# mouse.net
KiCad netlist of a schematic drawn in EasyEDA Pro
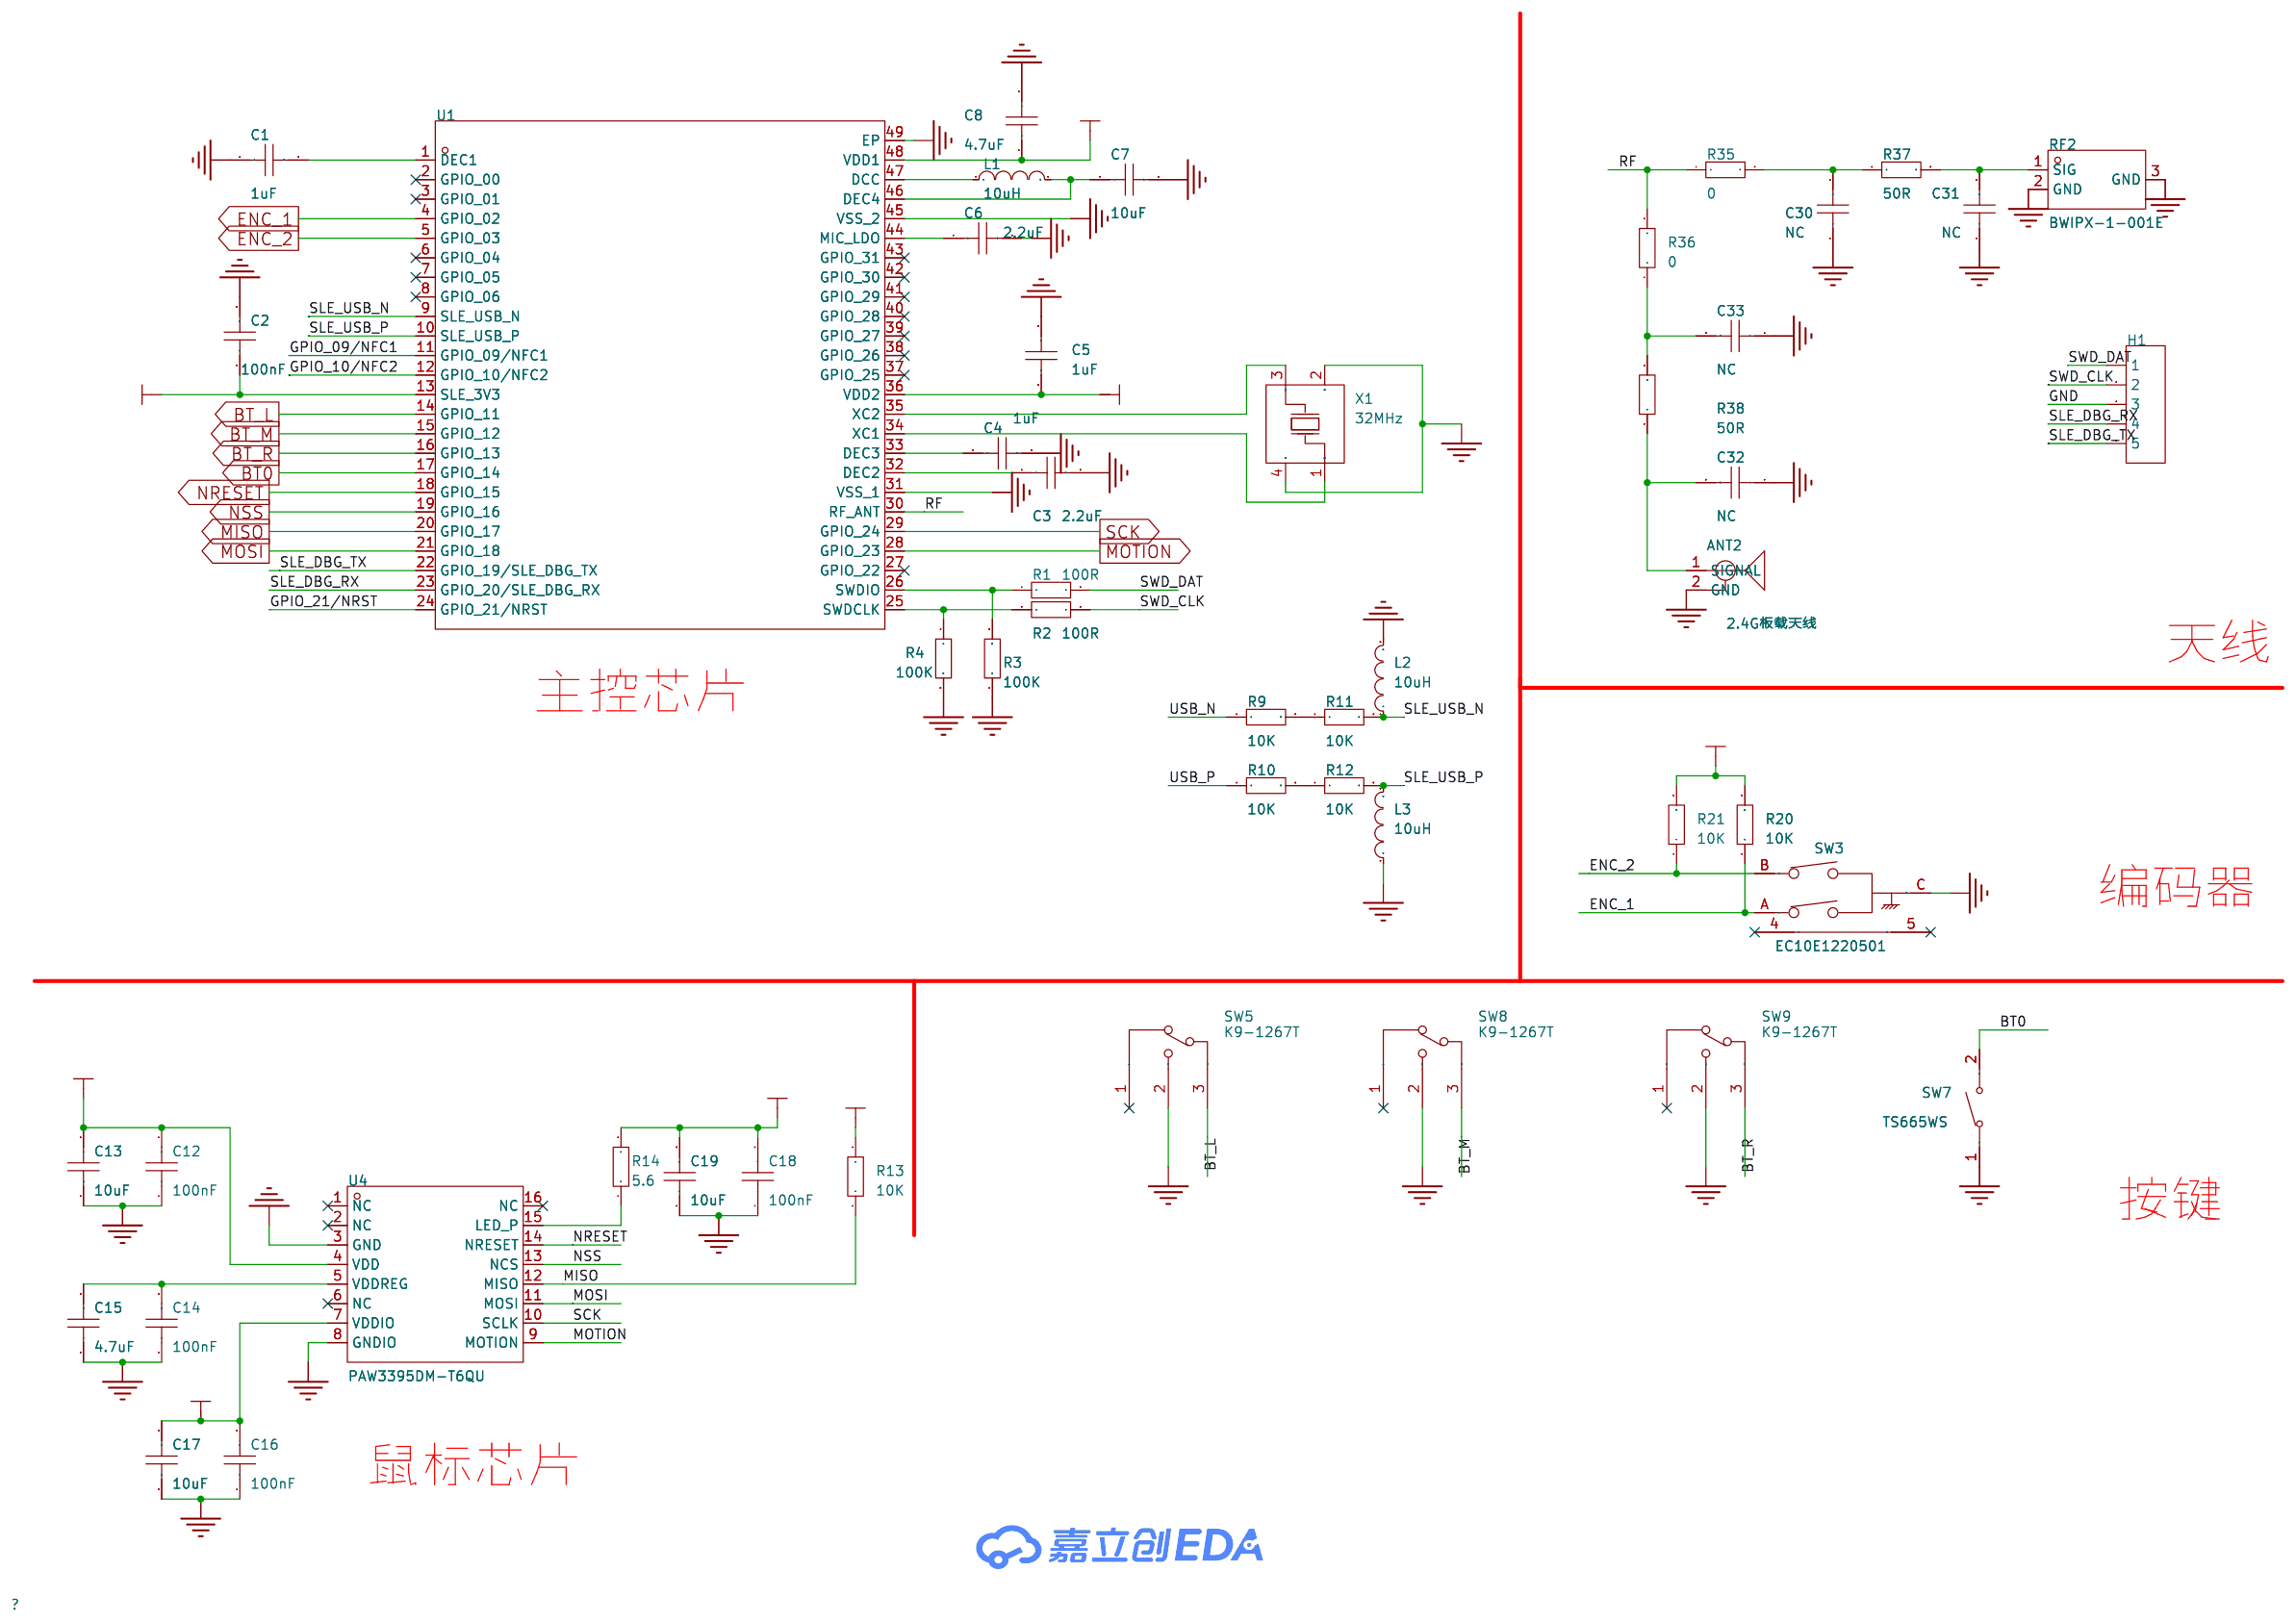
[diagram p0: P1]
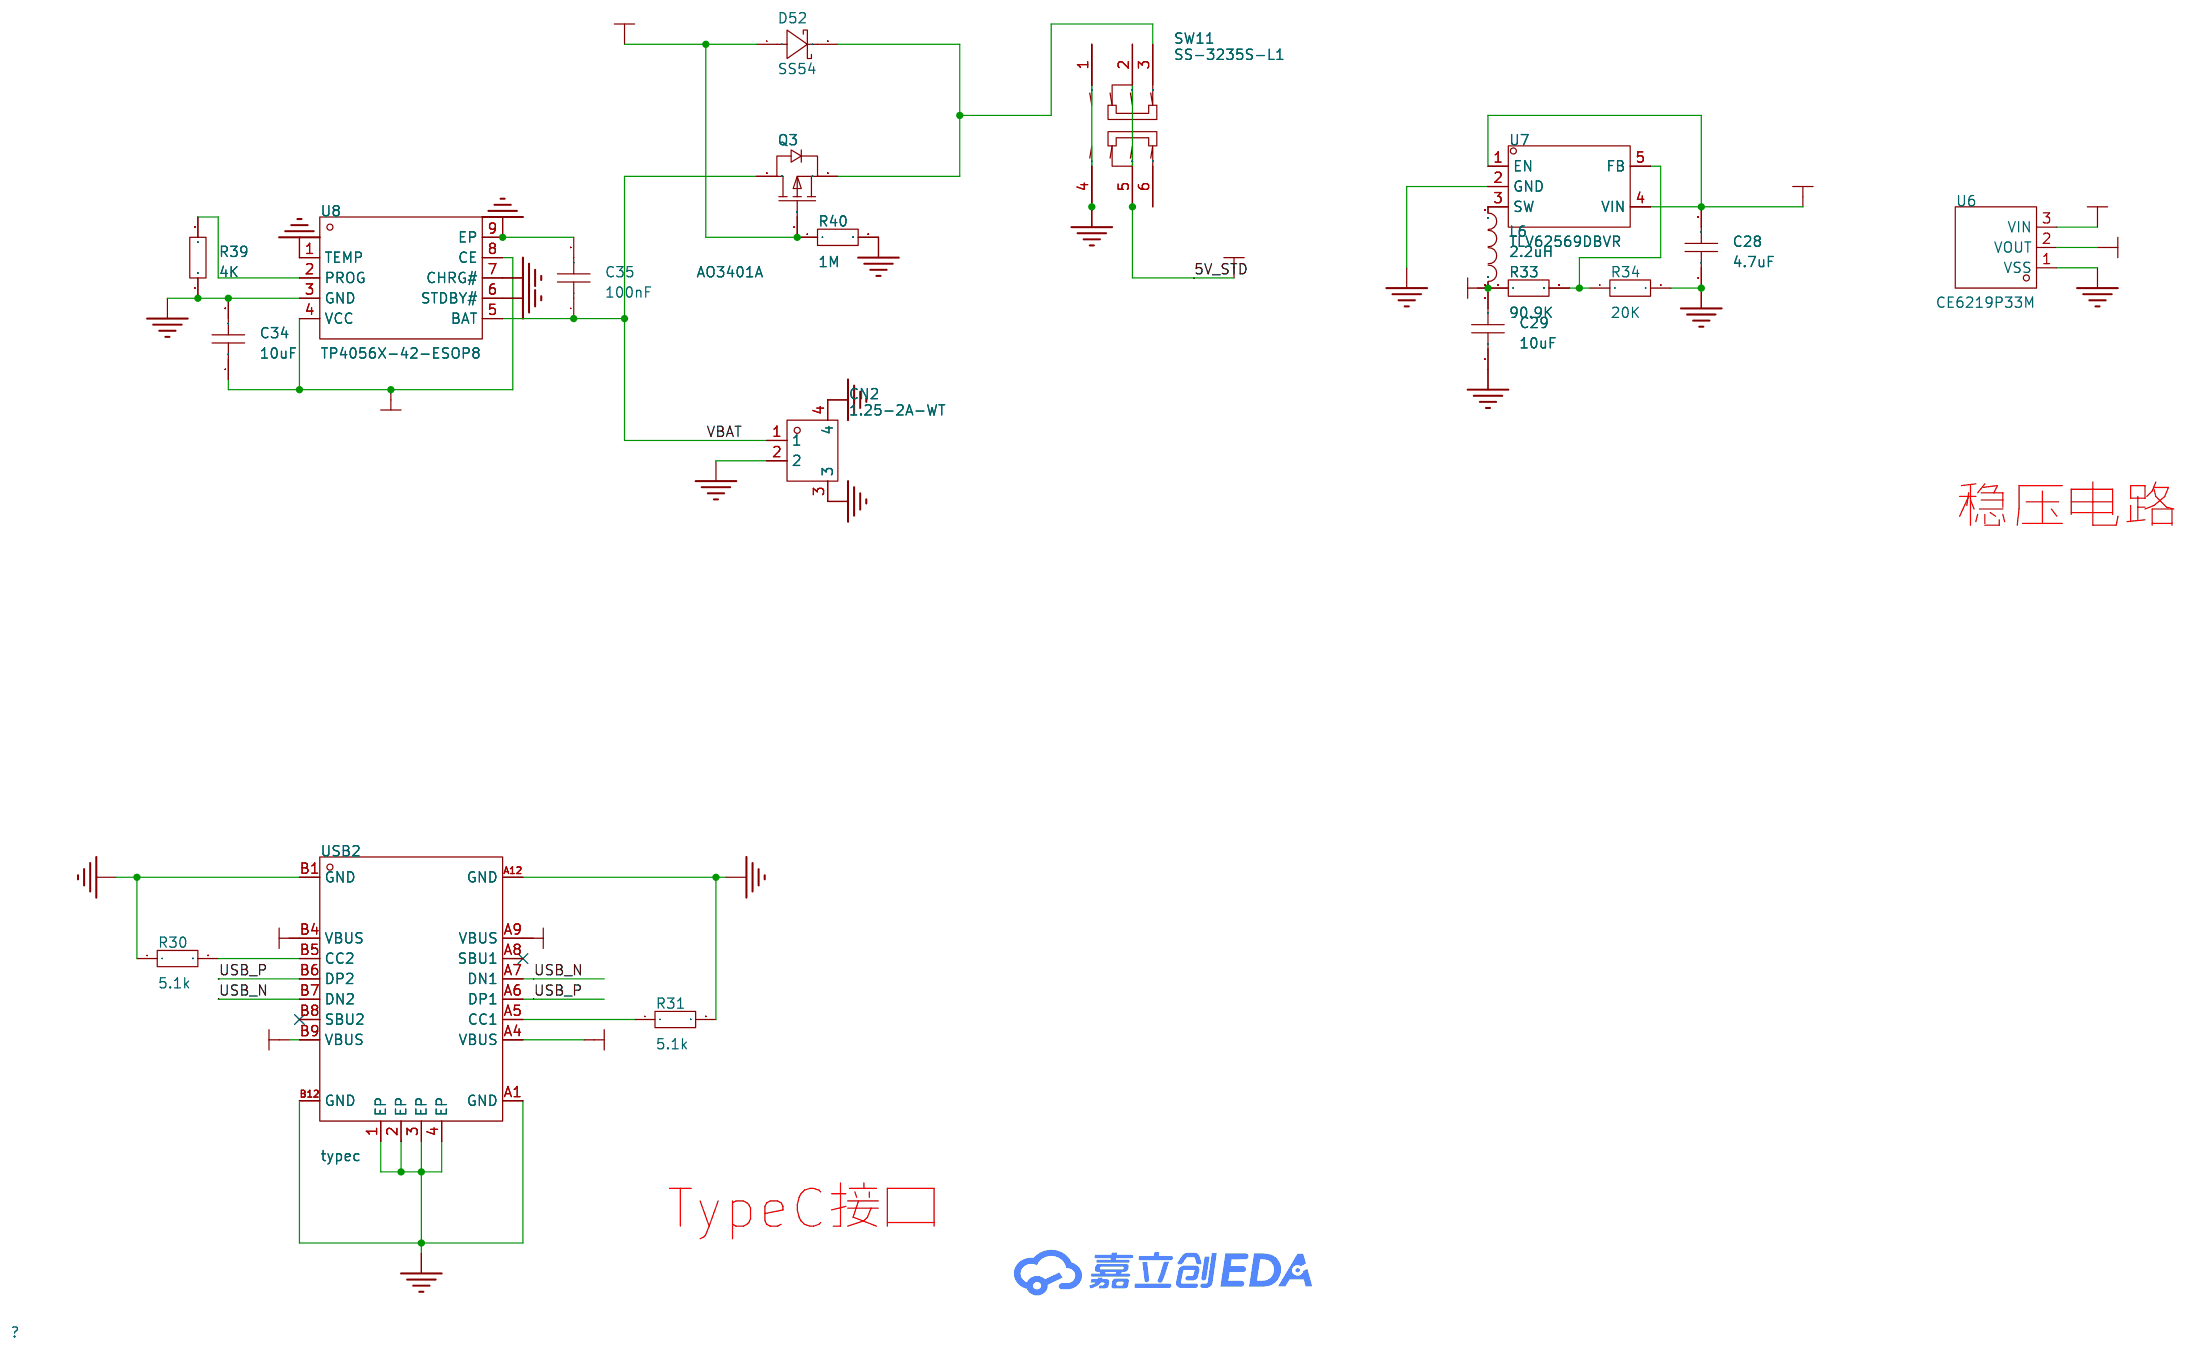
[diagram p1: P2]

(export (version "E")
  (design (tool "Eeschema 10.0.6"))
  (components
    (comp (ref "ANT2")
      (value "2.4G板载天线")
      (footprint "easyedapro:ANT-2.4G")
      (libsource (lib "easyedapro") (part "2.4G板载天线"))
    )
    (comp (ref "C1")
      (value "1uF")
      (footprint "easyedapro:C0402")
      (libsource (lib "easyedapro") (part "CapAcitance"))
    )
    (comp (ref "C2")
      (value "100nF")
      (footprint "easyedapro:C0402")
      (libsource (lib "easyedapro") (part "CapAcitance"))
    )
    (comp (ref "C3")
      (value "2.2uF")
      (footprint "easyedapro:C0402")
      (libsource (lib "easyedapro") (part "CapAcitance"))
    )
    (comp (ref "C4")
      (value "1uF")
      (footprint "easyedapro:C0402")
      (libsource (lib "easyedapro") (part "CapAcitance"))
    )
    (comp (ref "C5")
      (value "1uF")
      (footprint "easyedapro:C0402")
      (libsource (lib "easyedapro") (part "CapAcitance"))
    )
    (comp (ref "C6")
      (value "2.2uF")
      (footprint "easyedapro:C0402")
      (libsource (lib "easyedapro") (part "CapAcitance"))
    )
    (comp (ref "C7")
      (value "10uF")
      (footprint "easyedapro:C0402")
      (libsource (lib "easyedapro") (part "CapAcitance"))
    )
    (comp (ref "C8")
      (value "4.7uF")
      (footprint "easyedapro:C0402")
      (libsource (lib "easyedapro") (part "CapAcitance"))
    )
    (comp (ref "C12")
      (value "100nF")
      (footprint "easyedapro:C0402")
      (libsource (lib "easyedapro") (part "CapAcitance"))
    )
    (comp (ref "C13")
      (value "10uF")
      (footprint "easyedapro:C0402")
      (libsource (lib "easyedapro") (part "CapAcitance"))
    )
    (comp (ref "C14")
      (value "100nF")
      (footprint "easyedapro:C0402")
      (libsource (lib "easyedapro") (part "CapAcitance"))
    )
    (comp (ref "C15")
      (value "4.7uF")
      (footprint "easyedapro:C0402")
      (libsource (lib "easyedapro") (part "CapAcitance"))
    )
    (comp (ref "C16")
      (value "100nF")
      (footprint "easyedapro:C0402")
      (libsource (lib "easyedapro") (part "CapAcitance"))
    )
    (comp (ref "C17")
      (value "10uF")
      (footprint "easyedapro:C0402")
      (libsource (lib "easyedapro") (part "CapAcitance"))
    )
    (comp (ref "C18")
      (value "100nF")
      (footprint "easyedapro:C0402")
      (libsource (lib "easyedapro") (part "CapAcitance"))
    )
    (comp (ref "C19")
      (value "10uF")
      (footprint "easyedapro:C0402")
      (libsource (lib "easyedapro") (part "CapAcitance"))
    )
    (comp (ref "C30")
      (value "NC")
      (footprint "easyedapro:C0402")
      (libsource (lib "easyedapro") (part "CapAcitance"))
    )
    (comp (ref "C31")
      (value "NC")
      (footprint "easyedapro:C0402")
      (libsource (lib "easyedapro") (part "CapAcitance"))
    )
    (comp (ref "C32")
      (value "NC")
      (footprint "easyedapro:C0402")
      (libsource (lib "easyedapro") (part "CapAcitance"))
    )
    (comp (ref "C33")
      (value "NC")
      (footprint "easyedapro:C0402")
      (libsource (lib "easyedapro") (part "CapAcitance"))
    )
    (comp (ref "H1")
      (value "~")
      (footprint "easyedapro:HDR-TH_5P-P2.54-V-F")
      (libsource (lib "easyedapro") (part "Header-Female-2.54_1x5"))
    )
    (comp (ref "L1")
      (value "10uH")
      (footprint "easyedapro:L0805")
      (libsource (lib "easyedapro") (part "SDFL2012S100KTF"))
    )
    (comp (ref "L2")
      (value "10uH")
      (footprint "easyedapro:L0603")
      (libsource (lib "easyedapro") (part "SDFL1608S100KTF"))
    )
    (comp (ref "L3")
      (value "10uH")
      (footprint "easyedapro:L0603")
      (libsource (lib "easyedapro") (part "SDFL1608S100KTF"))
    )
    (comp (ref "R1") (value "100R") (footprint "easyedapro:R0603") (libsource (lib "easyedapro") (part "电阻")))
    (comp (ref "R2") (value "100R") (footprint "easyedapro:R0603") (libsource (lib "easyedapro") (part "电阻")))
    (comp (ref "R3") (value "100K") (footprint "easyedapro:R0603") (libsource (lib "easyedapro") (part "电阻")))
    (comp (ref "R4") (value "100K") (footprint "easyedapro:R0603") (libsource (lib "easyedapro") (part "电阻")))
    (comp (ref "R9") (value "10K") (footprint "easyedapro:R0603") (libsource (lib "easyedapro") (part "电阻")))
    (comp (ref "R10") (value "10K") (footprint "easyedapro:R0603") (libsource (lib "easyedapro") (part "电阻")))
    (comp (ref "R11") (value "10K") (footprint "easyedapro:R0603") (libsource (lib "easyedapro") (part "电阻")))
    (comp (ref "R12") (value "10K") (footprint "easyedapro:R0603") (libsource (lib "easyedapro") (part "电阻")))
    (comp (ref "R13") (value "10K") (footprint "easyedapro:R0603") (libsource (lib "easyedapro") (part "电阻")))
    (comp (ref "R14") (value "5.6") (footprint "easyedapro:R0603") (libsource (lib "easyedapro") (part "电阻")))
    (comp (ref "R20") (value "10K") (footprint "easyedapro:R0603") (libsource (lib "easyedapro") (part "电阻")))
    (comp (ref "R21") (value "10K") (footprint "easyedapro:R0603") (libsource (lib "easyedapro") (part "电阻")))
    (comp (ref "R35") (value "0") (footprint "easyedapro:R0603") (libsource (lib "easyedapro") (part "电阻")))
    (comp (ref "R36") (value "0") (footprint "easyedapro:R0603") (libsource (lib "easyedapro") (part "电阻")))
    (comp (ref "R37") (value "50R") (footprint "easyedapro:R0603") (libsource (lib "easyedapro") (part "电阻")))
    (comp (ref "R38") (value "50R") (footprint "easyedapro:R0603") (libsource (lib "easyedapro") (part "电阻")))
    (comp (ref "RF2")
      (value "BWIPX-1-001E")
      (footprint "easyedapro:IPEX-SMD_BWIPX-1-001E")
      (description "连接器类型:板端;接口类型:内针;端口数量:1;接口直径:-;接口长度/高度:-;频率-最大值:6GHz;射频系列:IPEX;阻抗:50Ω;样式:-;工作温度范围:-;")
      (fields (field (name "Manufacturer") "BAT WIRELESS(蝙蝠无线)"))
      (libsource (lib "easyedapro") (part "BWIPX-1-001E"))
    )
    (comp (ref "SW3")
      (value "EC10E1220501")
      (footprint "easyedapro:SW-TH_EC10EXXXXXXX")
      (description "10型贯通轴型")
      (fields (field (name "Manufacturer") "ALPSALPINE(阿尔卑斯阿尔派)"))
      (libsource (lib "easyedapro") (part "EC10E1220501"))
    )
    (comp (ref "SW5")
      (value "K9-1267T")
      (footprint "easyedapro:SW-TH_K9-1267T")
      (description "类型:微动开关;电路结构:单刀双掷;额定电流(DC):100mA;额定电压(DC):30V;额定电流(AC):-;额定电压(AC):-;机械寿命:300万次;")
      (fields (field (name "Manufacturer") "韩国韩荣"))
      (libsource (lib "easyedapro") (part "K9-1267T"))
    )
    (comp (ref "SW7")
      (value "TS665WS")
      (footprint "easyedapro:SW-SMD_L6.0-W6.0-LS6.6")
      (fields (field (name "Manufacturer") "SHOU HAN(首韩)"))
      (libsource (lib "easyedapro") (part "TS665WS"))
    )
    (comp (ref "SW8")
      (value "K9-1267T")
      (footprint "easyedapro:SW-TH_K9-1267T")
      (description "类型:微动开关;电路结构:单刀双掷;额定电流(DC):100mA;额定电压(DC):30V;额定电流(AC):-;额定电压(AC):-;机械寿命:300万次;")
      (fields (field (name "Manufacturer") "韩国韩荣"))
      (libsource (lib "easyedapro") (part "K9-1267T"))
    )
    (comp (ref "SW9")
      (value "K9-1267T")
      (footprint "easyedapro:SW-TH_K9-1267T")
      (description "类型:微动开关;电路结构:单刀双掷;额定电流(DC):100mA;额定电压(DC):30V;额定电流(AC):-;额定电压(AC):-;机械寿命:300万次;")
      (fields (field (name "Manufacturer") "韩国韩荣"))
      (libsource (lib "easyedapro") (part "K9-1267T"))
    )
    (comp (ref "U1")
      (value "~")
      (footprint "easyedapro:QFN-48_L6.0-W6.0-P0.40-TL-EP4.4")
      (fields (field (name "Manufacturer") "海思"))
      (libsource (lib "easyedapro") (part "hi2821"))
    )
    (comp (ref "U4")
      (value "PAW3395DM-T6QU")
      (footprint "easyedapro:DIP-16_PAW3395DM-T6QU")
      (libsource (lib "easyedapro") (part "PAW3395DM-T6QU"))
    )
    (comp (ref "X1")
      (value "32MHz")
      (footprint "easyedapro:OSC-SMD_4P-L2.0-W1.6-BL")
      (description "晶振类型:贴片晶振;频率:32MHz;常温频差:±20ppm;外接负载电容:8pF;频率稳定度(全温):±20ppm;")
      (fields (field (name "Manufacturer Part") "X201632MKD4SI") (field (name "Manufacturer") "YXC(扬兴晶振)"))
      (libsource (lib "easyedapro") (part "X201632MKD4SI"))
    )
    (comp (ref "C28")
      (value "4.7uF")
      (footprint "easyedapro:C0402")
      (libsource (lib "easyedapro") (part "CapAcitance"))
    )
    (comp (ref "C29")
      (value "10uF")
      (footprint "easyedapro:C0402")
      (libsource (lib "easyedapro") (part "CapAcitance"))
    )
    (comp (ref "C34")
      (value "10uF")
      (footprint "easyedapro:C0402")
      (libsource (lib "easyedapro") (part "CapAcitance"))
    )
    (comp (ref "C35")
      (value "100nF")
      (footprint "easyedapro:C0402")
      (libsource (lib "easyedapro") (part "CapAcitance"))
    )
    (comp (ref "CN2")
      (value "1.25-2A-WT")
      (footprint "easyedapro:CONN-TH_1.25-2A-WT")
      (description "插针结构:1x2P;间距:1.25mm;安装方式:卧贴;参考系列:-;总PIN数:2P;排数:1;每排PIN数:2;行距:-;额定电流:500mA;工作温度范围:-25°C~+85°C;")
      (fields (field (name "Manufacturer") "CAX(创都)"))
      (libsource (lib "easyedapro") (part "1.25-2A-WT"))
    )
    (comp (ref "D52")
      (value "SS54")
      (footprint "easyedapro:SMA_L4.3-W2.6-LS5.0-FD")
      (description "二极管配置:独立式;正向压降(Vf):550mV@5.0A;直流反向耐压(Vr):40V;整流电流:5A;")
      (fields (field (name "Manufacturer") "宏迦橙"))
      (libsource (lib "easyedapro") (part "SS54_C7420369"))
    )
    (comp (ref "L6")
      (value "2.2uH")
      (footprint "easyedapro:IND-SMD_L4.4-W4.2")
      (description "电感值:2.2uH;精度:±20%;额定电流:4.5A;饱和电流(Isat):5A;类型:一体成型电感;")
      (fields (field (name "Manufacturer Part") "FXL0420-2R2-M") (field (name "Manufacturer") "cjiang(长江微电)"))
      (libsource (lib "easyedapro") (part "FXL0420-2R2-M"))
    )
    (comp (ref "Q3")
      (value "AO3401A")
      (footprint "easyedapro:SOT-23_L2.9-W1.3-P1.90-LS2.4-BR")
      (fields (field (name "Manufacturer") "AOS"))
      (libsource (lib "easyedapro") (part "AO3401A"))
    )
    (comp (ref "R30")
      (value "5.1k")
      (footprint "easyedapro:R0603")
      (libsource (lib "easyedapro") (part "电阻"))
    )
    (comp (ref "R31")
      (value "5.1k")
      (footprint "easyedapro:R0603")
      (libsource (lib "easyedapro") (part "电阻"))
    )
    (comp (ref "R33")
      (value "90.9K")
      (footprint "easyedapro:R0603")
      (libsource (lib "easyedapro") (part "电阻"))
    )
    (comp (ref "R34") (value "20K") (footprint "easyedapro:R0603") (libsource (lib "easyedapro") (part "电阻")))
    (comp (ref "R39") (value "4K") (footprint "easyedapro:R0603") (libsource (lib "easyedapro") (part "电阻")))
    (comp (ref "R40") (value "1M") (footprint "easyedapro:R0603") (libsource (lib "easyedapro") (part "电阻")))
    (comp (ref "SW11")
      (value "SS-3235S-L1")
      (footprint "easyedapro:SW-SMD_SS-3235S-LX")
      (description "电路结构:双刀双掷;安装方式:卧贴;开关颜色:黑色;额定电流(DC):50mA;额定电压(DC):12V;额定电流(AC):50mA;额定电压(AC):12V;机械寿命:1万次;")
      (fields (field (name "Manufacturer") "XKB Connectivity(中国星坤)"))
      (libsource (lib "easyedapro") (part "SS-3235S-L1"))
    )
    (comp (ref "U6")
      (value "CE6219P33M")
      (footprint "easyedapro:SOT-23-3_L2.9-W1.6-P1.90-LS2.8-BR")
      (libsource (lib "easyedapro") (part "CE6219P33M"))
    )
    (comp (ref "U7")
      (value "TLV62569DBVR")
      (footprint "easyedapro:SOT-23-5_L3.0-W1.7-P0.95-LS2.8-BR")
      (description "功能类型:降压型;输出类型:可调;输入电压:2.5V~5.5V;输出电压:600mV~5.5V;输出电流(最大值):2A;")
      (fields (field (name "Manufacturer") "TI(德州仪器)"))
      (libsource (lib "easyedapro") (part "TLV62569DBVR"))
    )
    (comp (ref "U8")
      (value "TP4056X-42-ESOP8")
      (footprint "easyedapro:SOP-8_L4.9-W3.9-P1.27-LS6.0-TL-EP")
      (fields (field (name "Manufacturer") "TOPPOWER(南京拓微)"))
      (libsource (lib "easyedapro") (part "TP4056X_C2763448"))
    )
    (comp (ref "USB2")
      (value "typec")
      (footprint "easyedapro:USB-C-SMD_KH-TYPE-C-16P")
      (libsource (lib "easyedapro") (part "TYPEC_C9900016956"))
    )
  )
  (nets
    (net (code "1") (name "5V") (class "Default")
      (node (ref "C34") (pin "1") (pinfunction "1_1") (pintype "input"))
      (node (ref "D52") (pin "1") (pinfunction "A_1") (pintype "unspecified"))
      (node (ref "Q3") (pin "1") (pinfunction "G_1") (pintype "unspecified"))
      (node (ref "R20") (pin "2") (pinfunction "2_2") (pintype "input"))
      (node (ref "R21") (pin "2") (pinfunction "2_2") (pintype "input"))
      (node (ref "R40") (pin "1") (pinfunction "1_1") (pintype "input"))
      (node (ref "U8") (pin "4") (pinfunction "VCC_4") (pintype "input"))
      (node (ref "U8") (pin "8") (pinfunction "CE_8") (pintype "input"))
      (node (ref "USB2") (pin "A4") (pinfunction "VBUS_A4") (pintype "unspecified"))
      (node (ref "USB2") (pin "A9") (pinfunction "VBUS_A9") (pintype "unspecified"))
      (node (ref "USB2") (pin "B4") (pinfunction "VBUS_B4") (pintype "unspecified"))
      (node (ref "USB2") (pin "B9") (pinfunction "VBUS_B9") (pintype "unspecified"))
    )
    (net (code "2") (name "5V_STD") (class "Default")
      (node (ref "C28") (pin "2") (pinfunction "2_2") (pintype "input"))
      (node (ref "SW11") (pin "2") (pinfunction "2_2") (pintype "unspecified"))
      (node (ref "SW11") (pin "5") (pinfunction "5_5") (pintype "unspecified"))
      (node (ref "U7") (pin "1") (pinfunction "EN_1") (pintype "unspecified"))
      (node (ref "U7") (pin "4") (pinfunction "VIN_4") (pintype "unspecified"))
    )
    (net (code "3") (name "BT0") (class "Default")
      (node (ref "SW7") (pin "2") (pinfunction "B_2") (pintype "unspecified"))
      (node (ref "U1") (pin "17") (pinfunction "GPIO_14_17") (pintype "unspecified"))
    )
    (net (code "4") (name "BT_L") (class "Default")
      (node (ref "SW5") (pin "3") (pinfunction "NC_3") (pintype "unspecified"))
      (node (ref "U1") (pin "14") (pinfunction "GPIO_11_14") (pintype "unspecified"))
    )
    (net (code "5") (name "BT_M") (class "Default")
      (node (ref "SW8") (pin "3") (pinfunction "NC_3") (pintype "unspecified"))
      (node (ref "U1") (pin "15") (pinfunction "GPIO_12_15") (pintype "unspecified"))
    )
    (net (code "6") (name "BT_R") (class "Default")
      (node (ref "SW9") (pin "3") (pinfunction "NC_3") (pintype "unspecified"))
      (node (ref "U1") (pin "16") (pinfunction "GPIO_13_16") (pintype "unspecified"))
    )
    (net (code "7") (name "ENC_1") (class "Default")
      (node (ref "R20") (pin "1") (pinfunction "1_1") (pintype "input"))
      (node (ref "SW3") (pin "A") (pinfunction "A_A") (pintype "input"))
      (node (ref "U1") (pin "4") (pinfunction "GPIO_02_4") (pintype "unspecified"))
    )
    (net (code "8") (name "ENC_2") (class "Default")
      (node (ref "R21") (pin "1") (pinfunction "1_1") (pintype "input"))
      (node (ref "SW3") (pin "B") (pinfunction "B_B") (pintype "input"))
      (node (ref "U1") (pin "5") (pinfunction "GPIO_03_5") (pintype "unspecified"))
    )
    (net (code "9") (name "GND") (class "Default")
      (node (ref "ANT2") (pin "2") (pinfunction "GND_2") (pintype "unspecified"))
      (node (ref "C1") (pin "1") (pinfunction "1_1") (pintype "input"))
      (node (ref "C12") (pin "1") (pinfunction "1_1") (pintype "input"))
      (node (ref "C13") (pin "1") (pinfunction "1_1") (pintype "input"))
      (node (ref "C14") (pin "1") (pinfunction "1_1") (pintype "input"))
      (node (ref "C15") (pin "1") (pinfunction "1_1") (pintype "input"))
      (node (ref "C16") (pin "1") (pinfunction "1_1") (pintype "input"))
      (node (ref "C17") (pin "1") (pinfunction "1_1") (pintype "input"))
      (node (ref "C18") (pin "1") (pinfunction "1_1") (pintype "input"))
      (node (ref "C19") (pin "1") (pinfunction "1_1") (pintype "input"))
      (node (ref "C2") (pin "2") (pinfunction "2_2") (pintype "input"))
      (node (ref "C28") (pin "1") (pinfunction "1_1") (pintype "input"))
      (node (ref "C29") (pin "1") (pinfunction "1_1") (pintype "input"))
      (node (ref "C3") (pin "2") (pinfunction "2_2") (pintype "input"))
      (node (ref "C30") (pin "1") (pinfunction "1_1") (pintype "input"))
      (node (ref "C31") (pin "1") (pinfunction "1_1") (pintype "input"))
      (node (ref "C32") (pin "1") (pinfunction "1_1") (pintype "input"))
      (node (ref "C33") (pin "1") (pinfunction "1_1") (pintype "input"))
      (node (ref "C34") (pin "2") (pinfunction "2_2") (pintype "input"))
      (node (ref "C35") (pin "2") (pinfunction "2_2") (pintype "input"))
      (node (ref "C4") (pin "2") (pinfunction "2_2") (pintype "input"))
      (node (ref "C5") (pin "2") (pinfunction "2_2") (pintype "input"))
      (node (ref "C6") (pin "2") (pinfunction "2_2") (pintype "input"))
      (node (ref "C7") (pin "2") (pinfunction "2_2") (pintype "input"))
      (node (ref "C8") (pin "2") (pinfunction "2_2") (pintype "input"))
      (node (ref "CN2") (pin "2") (pinfunction "2_2") (pintype "unspecified"))
      (node (ref "CN2") (pin "3") (pinfunction "3_3") (pintype "unspecified"))
      (node (ref "CN2") (pin "4") (pinfunction "4_4") (pintype "unspecified"))
      (node (ref "H1") (pin "3") (pinfunction "3_3") (pintype "input"))
      (node (ref "L2") (pin "2") (pinfunction "2_2") (pintype "unspecified"))
      (node (ref "L3") (pin "1") (pinfunction "1_1") (pintype "unspecified"))
      (node (ref "R3") (pin "1") (pinfunction "1_1") (pintype "input"))
      (node (ref "R30") (pin "1") (pinfunction "1_1") (pintype "input"))
      (node (ref "R31") (pin "2") (pinfunction "2_2") (pintype "input"))
      (node (ref "R34") (pin "2") (pinfunction "2_2") (pintype "input"))
      (node (ref "R39") (pin "1") (pinfunction "1_1") (pintype "input"))
      (node (ref "R4") (pin "2") (pinfunction "2_2") (pintype "input"))
      (node (ref "R40") (pin "2") (pinfunction "2_2") (pintype "input"))
      (node (ref "RF2") (pin "2") (pinfunction "GND_2") (pintype "unspecified"))
      (node (ref "RF2") (pin "3") (pinfunction "GND_3") (pintype "unspecified"))
      (node (ref "SW11") (pin "1") (pinfunction "1_1") (pintype "unspecified"))
      (node (ref "SW11") (pin "4") (pinfunction "4_4") (pintype "unspecified"))
      (node (ref "SW3") (pin "C") (pinfunction "C_C") (pintype "input"))
      (node (ref "SW5") (pin "2") (pinfunction "ON_2") (pintype "unspecified"))
      (node (ref "SW7") (pin "1") (pinfunction "A_1") (pintype "unspecified"))
      (node (ref "SW8") (pin "2") (pinfunction "ON_2") (pintype "unspecified"))
      (node (ref "SW9") (pin "2") (pinfunction "ON_2") (pintype "unspecified"))
      (node (ref "U1") (pin "31") (pinfunction "VSS_1_31") (pintype "unspecified"))
      (node (ref "U1") (pin "45") (pinfunction "VSS_2_45") (pintype "unspecified"))
      (node (ref "U1") (pin "49") (pinfunction "EP_49") (pintype "unspecified"))
      (node (ref "U4") (pin "3") (pinfunction "GND_3") (pintype "input"))
      (node (ref "U4") (pin "8") (pinfunction "GNDIO_8") (pintype "input"))
      (node (ref "U6") (pin "1") (pinfunction "VSS_1") (pintype "input"))
      (node (ref "U7") (pin "2") (pinfunction "GND_2") (pintype "unspecified"))
      (node (ref "U8") (pin "1") (pinfunction "TEMP_1") (pintype "input"))
      (node (ref "U8") (pin "3") (pinfunction "GND_3") (pintype "input"))
      (node (ref "U8") (pin "6") (pinfunction "STDBY#_6") (pintype "input"))
      (node (ref "U8") (pin "7") (pinfunction "CHRG#_7") (pintype "input"))
      (node (ref "U8") (pin "9") (pinfunction "EP_9") (pintype "input"))
      (node (ref "USB2") (pin "1") (pinfunction "EP_1") (pintype "unspecified"))
      (node (ref "USB2") (pin "2") (pinfunction "EP_2") (pintype "unspecified"))
      (node (ref "USB2") (pin "3") (pinfunction "EP_3") (pintype "unspecified"))
      (node (ref "USB2") (pin "4") (pinfunction "EP_4") (pintype "unspecified"))
      (node (ref "USB2") (pin "A1") (pinfunction "GND_A1") (pintype "unspecified"))
      (node (ref "USB2") (pin "A12") (pinfunction "GND_A12") (pintype "unspecified"))
      (node (ref "USB2") (pin "B1") (pinfunction "GND_B1") (pintype "unspecified"))
      (node (ref "USB2") (pin "B12") (pinfunction "GND_B12") (pintype "unspecified"))
      (node (ref "X1") (pin "2") (pinfunction "GND_2") (pintype "input"))
      (node (ref "X1") (pin "4") (pinfunction "GND_4") (pintype "input"))
    )
    (net (code "10") (name "GPIO_09{slash}NFC1") (class "Default")
      (node (ref "U1") (pin "11") (pinfunction "GPIO_09/NFC1_11") (pintype "unspecified"))
    )
    (net (code "11") (name "GPIO_10{slash}NFC2") (class "Default")
      (node (ref "U1") (pin "12") (pinfunction "GPIO_10/NFC2_12") (pintype "unspecified"))
    )
    (net (code "12") (name "GPIO_21{slash}NRST") (class "Default")
      (node (ref "U1") (pin "24") (pinfunction "GPIO_21/NRST_24") (pintype "unspecified"))
    )
    (net (code "13") (name "MISO") (class "Default")
      (node (ref "R13") (pin "1") (pinfunction "1_1") (pintype "input"))
      (node (ref "U1") (pin "20") (pinfunction "GPIO_17_20") (pintype "unspecified"))
      (node (ref "U4") (pin "12") (pinfunction "MISO_12") (pintype "input"))
    )
    (net (code "14") (name "MOSI") (class "Default")
      (node (ref "U1") (pin "21") (pinfunction "GPIO_18_21") (pintype "unspecified"))
      (node (ref "U4") (pin "11") (pinfunction "MOSI_11") (pintype "input"))
    )
    (net (code "15") (name "MOTION") (class "Default")
      (node (ref "U1") (pin "28") (pinfunction "GPIO_23_28") (pintype "unspecified"))
      (node (ref "U4") (pin "9") (pinfunction "MOTION_9") (pintype "input"))
    )
    (net (code "16") (name "NRESET") (class "Default")
      (node (ref "U1") (pin "18") (pinfunction "GPIO_15_18") (pintype "unspecified"))
      (node (ref "U4") (pin "14") (pinfunction "NRESET_14") (pintype "input"))
    )
    (net (code "17") (name "NSS") (class "Default")
      (node (ref "U1") (pin "19") (pinfunction "GPIO_16_19") (pintype "unspecified"))
      (node (ref "U4") (pin "13") (pinfunction "NCS_13") (pintype "input"))
    )
    (net (code "18") (name "Net-(ANT2-SIGNAL)") (class "Default")
      (node (ref "ANT2") (pin "1") (pinfunction "SIGNAL_1") (pintype "unspecified"))
      (node (ref "C32") (pin "2") (pinfunction "2_2") (pintype "input"))
      (node (ref "R38") (pin "1") (pinfunction "1_1") (pintype "input"))
    )
    (net (code "19") (name "Net-(C30-Pad2)") (class "Default")
      (node (ref "C30") (pin "2") (pinfunction "2_2") (pintype "input"))
      (node (ref "R35") (pin "2") (pinfunction "2_2") (pintype "input"))
      (node (ref "R37") (pin "1") (pinfunction "1_1") (pintype "input"))
    )
    (net (code "20") (name "Net-(C33-Pad2)") (class "Default")
      (node (ref "C33") (pin "2") (pinfunction "2_2") (pintype "input"))
      (node (ref "R36") (pin "1") (pinfunction "1_1") (pintype "input"))
      (node (ref "R38") (pin "2") (pinfunction "2_2") (pintype "input"))
    )
    (net (code "21") (name "Net-(D52-K)") (class "Default")
      (node (ref "D52") (pin "2") (pinfunction "K_2") (pintype "unspecified"))
      (node (ref "Q3") (pin "2") (pinfunction "S_2") (pintype "unspecified"))
      (node (ref "SW11") (pin "3") (pinfunction "3_3") (pintype "unspecified"))
    )
    (net (code "22") (name "Net-(R10-Pad2)") (class "Default")
      (node (ref "R10") (pin "2") (pinfunction "2_2") (pintype "input"))
      (node (ref "R12") (pin "1") (pinfunction "1_1") (pintype "input"))
    )
    (net (code "23") (name "Net-(R11-Pad1)") (class "Default")
      (node (ref "R11") (pin "1") (pinfunction "1_1") (pintype "input"))
      (node (ref "R9") (pin "2") (pinfunction "2_2") (pintype "input"))
    )
    (net (code "24") (name "Net-(RF2-SIG)") (class "Default")
      (node (ref "C31") (pin "2") (pinfunction "2_2") (pintype "input"))
      (node (ref "R37") (pin "2") (pinfunction "2_2") (pintype "input"))
      (node (ref "RF2") (pin "1") (pinfunction "SIG_1") (pintype "unspecified"))
    )
    (net (code "25") (name "Net-(U1-DCC)") (class "Default")
      (node (ref "L1") (pin "1") (pinfunction "1_1") (pintype "unspecified"))
      (node (ref "U1") (pin "47") (pinfunction "DCC_47") (pintype "unspecified"))
    )
    (net (code "26") (name "Net-(U1-DEC1)") (class "Default")
      (node (ref "C1") (pin "2") (pinfunction "2_2") (pintype "input"))
      (node (ref "U1") (pin "1") (pinfunction "DEC1_1") (pintype "unspecified"))
    )
    (net (code "27") (name "Net-(U1-DEC2)") (class "Default")
      (node (ref "C3") (pin "1") (pinfunction "1_1") (pintype "input"))
      (node (ref "U1") (pin "32") (pinfunction "DEC2_32") (pintype "unspecified"))
    )
    (net (code "28") (name "Net-(U1-DEC3)") (class "Default")
      (node (ref "C4") (pin "1") (pinfunction "1_1") (pintype "input"))
      (node (ref "U1") (pin "33") (pinfunction "DEC3_33") (pintype "unspecified"))
    )
    (net (code "29") (name "Net-(U1-DEC4)") (class "Default")
      (node (ref "C7") (pin "1") (pinfunction "1_1") (pintype "input"))
      (node (ref "L1") (pin "2") (pinfunction "2_2") (pintype "unspecified"))
      (node (ref "U1") (pin "46") (pinfunction "DEC4_46") (pintype "unspecified"))
    )
    (net (code "30") (name "Net-(U1-MIC_LDO)") (class "Default")
      (node (ref "C6") (pin "1") (pinfunction "1_1") (pintype "input"))
      (node (ref "U1") (pin "44") (pinfunction "MIC_LDO_44") (pintype "unspecified"))
    )
    (net (code "31") (name "Net-(U1-SWDCLK)") (class "Default")
      (node (ref "R2") (pin "1") (pinfunction "1_1") (pintype "input"))
      (node (ref "R4") (pin "1") (pinfunction "1_1") (pintype "input"))
      (node (ref "U1") (pin "25") (pinfunction "SWDCLK_25") (pintype "unspecified"))
    )
    (net (code "32") (name "Net-(U1-SWDIO)") (class "Default")
      (node (ref "R1") (pin "1") (pinfunction "1_1") (pintype "input"))
      (node (ref "R3") (pin "2") (pinfunction "2_2") (pintype "input"))
      (node (ref "U1") (pin "26") (pinfunction "SWDIO_26") (pintype "unspecified"))
    )
    (net (code "33") (name "Net-(U1-XC1)") (class "Default")
      (node (ref "U1") (pin "34") (pinfunction "XC1_34") (pintype "unspecified"))
      (node (ref "X1") (pin "1") (pinfunction "OSC1_1") (pintype "input"))
    )
    (net (code "34") (name "Net-(U1-XC2)") (class "Default")
      (node (ref "U1") (pin "35") (pinfunction "XC2_35") (pintype "unspecified"))
      (node (ref "X1") (pin "3") (pinfunction "OSC2_3") (pintype "input"))
    )
    (net (code "35") (name "Net-(U4-LED_P)") (class "Default")
      (node (ref "R14") (pin "1") (pinfunction "1_1") (pintype "input"))
      (node (ref "U4") (pin "15") (pinfunction "LED_P_15") (pintype "input"))
    )
    (net (code "36") (name "Net-(U4-VDDREG)") (class "Default")
      (node (ref "C14") (pin "2") (pinfunction "2_2") (pintype "input"))
      (node (ref "C15") (pin "2") (pinfunction "2_2") (pintype "input"))
      (node (ref "U4") (pin "5") (pinfunction "VDDREG_5") (pintype "input"))
    )
    (net (code "37") (name "Net-(U7-FB)") (class "Default")
      (node (ref "R33") (pin "2") (pinfunction "2_2") (pintype "input"))
      (node (ref "R34") (pin "1") (pinfunction "1_1") (pintype "input"))
      (node (ref "U7") (pin "5") (pinfunction "FB_5") (pintype "unspecified"))
    )
    (net (code "38") (name "Net-(U7-SW)") (class "Default")
      (node (ref "L6") (pin "1") (pinfunction "1_1") (pintype "unspecified"))
      (node (ref "U7") (pin "3") (pinfunction "SW_3") (pintype "unspecified"))
    )
    (net (code "39") (name "Net-(U8-PROG)") (class "Default")
      (node (ref "R39") (pin "2") (pinfunction "2_2") (pintype "input"))
      (node (ref "U8") (pin "2") (pinfunction "PROG_2") (pintype "input"))
    )
    (net (code "40") (name "Net-(USB2-CC1)") (class "Default")
      (node (ref "R31") (pin "1") (pinfunction "1_1") (pintype "input"))
      (node (ref "USB2") (pin "A5") (pinfunction "CC1_A5") (pintype "unspecified"))
    )
    (net (code "41") (name "Net-(USB2-CC2)") (class "Default")
      (node (ref "R30") (pin "2") (pinfunction "2_2") (pintype "input"))
      (node (ref "USB2") (pin "B5") (pinfunction "CC2_B5") (pintype "unspecified"))
    )
    (net (code "42") (name "RF") (class "Default")
      (node (ref "R35") (pin "1") (pinfunction "1_1") (pintype "input"))
      (node (ref "R36") (pin "2") (pinfunction "2_2") (pintype "input"))
      (node (ref "U1") (pin "30") (pinfunction "RF_ANT_30") (pintype "unspecified"))
    )
    (net (code "43") (name "SCK") (class "Default")
      (node (ref "U1") (pin "29") (pinfunction "GPIO_24_29") (pintype "unspecified"))
      (node (ref "U4") (pin "10") (pinfunction "SCLK_10") (pintype "input"))
    )
    (net (code "44") (name "SLE_3V3") (class "Default")
      (node (ref "C16") (pin "2") (pinfunction "2_2") (pintype "input"))
      (node (ref "C17") (pin "2") (pinfunction "2_2") (pintype "input"))
      (node (ref "C2") (pin "1") (pinfunction "1_1") (pintype "input"))
      (node (ref "C29") (pin "2") (pinfunction "2_2") (pintype "input"))
      (node (ref "C5") (pin "1") (pinfunction "1_1") (pintype "input"))
      (node (ref "C8") (pin "1") (pinfunction "1_1") (pintype "input"))
      (node (ref "L6") (pin "2") (pinfunction "2_2") (pintype "unspecified"))
      (node (ref "R13") (pin "2") (pinfunction "2_2") (pintype "input"))
      (node (ref "R33") (pin "1") (pinfunction "1_1") (pintype "input"))
      (node (ref "U1") (pin "13") (pinfunction "SLE_3V3_13") (pintype "unspecified"))
      (node (ref "U1") (pin "36") (pinfunction "VDD2_36") (pintype "unspecified"))
      (node (ref "U1") (pin "48") (pinfunction "VDD1_48") (pintype "unspecified"))
      (node (ref "U4") (pin "7") (pinfunction "VDDIO_7") (pintype "input"))
      (node (ref "U6") (pin "3") (pinfunction "VIN_3") (pintype "input"))
    )
    (net (code "45") (name "SLE_DBG_RX") (class "Default")
      (node (ref "H1") (pin "4") (pinfunction "4_4") (pintype "input"))
      (node (ref "U1") (pin "23") (pinfunction "GPIO_20/SLE_DBG_RX_23") (pintype "unspecified"))
    )
    (net (code "46") (name "SLE_DBG_TX") (class "Default")
      (node (ref "H1") (pin "5") (pinfunction "5_5") (pintype "input"))
      (node (ref "U1") (pin "22") (pinfunction "GPIO_19/SLE_DBG_TX_22") (pintype "unspecified"))
    )
    (net (code "47") (name "SLE_USB_N") (class "Default")
      (node (ref "L2") (pin "1") (pinfunction "1_1") (pintype "unspecified"))
      (node (ref "R11") (pin "2") (pinfunction "2_2") (pintype "input"))
      (node (ref "U1") (pin "9") (pinfunction "SLE_USB_N_9") (pintype "unspecified"))
    )
    (net (code "48") (name "SLE_USB_P") (class "Default")
      (node (ref "L3") (pin "2") (pinfunction "2_2") (pintype "unspecified"))
      (node (ref "R12") (pin "2") (pinfunction "2_2") (pintype "input"))
      (node (ref "U1") (pin "10") (pinfunction "SLE_USB_P_10") (pintype "unspecified"))
    )
    (net (code "49") (name "SWD_CLK") (class "Default")
      (node (ref "H1") (pin "2") (pinfunction "2_2") (pintype "input"))
      (node (ref "R2") (pin "2") (pinfunction "2_2") (pintype "input"))
    )
    (net (code "50") (name "SWD_DAT") (class "Default")
      (node (ref "H1") (pin "1") (pinfunction "1_1") (pintype "input"))
      (node (ref "R1") (pin "2") (pinfunction "2_2") (pintype "input"))
    )
    (net (code "51") (name "USB_N") (class "Default")
      (node (ref "R9") (pin "1") (pinfunction "1_1") (pintype "input"))
      (node (ref "USB2") (pin "A7") (pinfunction "DN1_A7") (pintype "unspecified"))
      (node (ref "USB2") (pin "B7") (pinfunction "DN2_B7") (pintype "unspecified"))
    )
    (net (code "52") (name "USB_P") (class "Default")
      (node (ref "R10") (pin "1") (pinfunction "1_1") (pintype "input"))
      (node (ref "USB2") (pin "A6") (pinfunction "DP1_A6") (pintype "unspecified"))
      (node (ref "USB2") (pin "B6") (pinfunction "DP2_B6") (pintype "unspecified"))
    )
    (net (code "53") (name "VBAT") (class "Default")
      (node (ref "C35") (pin "1") (pinfunction "1_1") (pintype "input"))
      (node (ref "CN2") (pin "1") (pinfunction "1_1") (pintype "unspecified"))
      (node (ref "Q3") (pin "3") (pinfunction "D_3") (pintype "unspecified"))
      (node (ref "U8") (pin "5") (pinfunction "BAT_5") (pintype "input"))
    )
    (net (code "54") (name "VDD_1.9V") (class "Default")
      (node (ref "C12") (pin "2") (pinfunction "2_2") (pintype "input"))
      (node (ref "C13") (pin "2") (pinfunction "2_2") (pintype "input"))
      (node (ref "C18") (pin "2") (pinfunction "2_2") (pintype "input"))
      (node (ref "C19") (pin "2") (pinfunction "2_2") (pintype "input"))
      (node (ref "R14") (pin "2") (pinfunction "2_2") (pintype "input"))
      (node (ref "U4") (pin "4") (pinfunction "VDD_4") (pintype "input"))
      (node (ref "U6") (pin "2") (pinfunction "VOUT_2") (pintype "input"))
    )
    (net (code "55") (name "unconnected-(SW3-Pad4)") (class "Default")
      (node (ref "SW3") (pin "4") (pinfunction "4_4") (pintype "input+no_connect"))
    )
    (net (code "56") (name "unconnected-(SW3-Pad5)") (class "Default")
      (node (ref "SW3") (pin "5") (pinfunction "5_5") (pintype "input+no_connect"))
    )
    (net (code "57") (name "unconnected-(SW5-C-Pad1)") (class "Default")
      (node (ref "SW5") (pin "1") (pinfunction "C_1") (pintype "unspecified+no_connect"))
    )
    (net (code "58") (name "unconnected-(SW8-C-Pad1)") (class "Default")
      (node (ref "SW8") (pin "1") (pinfunction "C_1") (pintype "unspecified+no_connect"))
    )
    (net (code "59") (name "unconnected-(SW9-C-Pad1)") (class "Default")
      (node (ref "SW9") (pin "1") (pinfunction "C_1") (pintype "unspecified+no_connect"))
    )
    (net (code "60") (name "unconnected-(SW11-Pad6)") (class "Default")
      (node (ref "SW11") (pin "6") (pinfunction "6_6") (pintype "unspecified"))
    )
    (net (code "61") (name "unconnected-(U1-GPIO_00-Pad2)") (class "Default")
      (node (ref "U1") (pin "2") (pinfunction "GPIO_00_2") (pintype "unspecified+no_connect"))
    )
    (net (code "62") (name "unconnected-(U1-GPIO_01-Pad3)") (class "Default")
      (node (ref "U1") (pin "3") (pinfunction "GPIO_01_3") (pintype "unspecified+no_connect"))
    )
    (net (code "63") (name "unconnected-(U1-GPIO_04-Pad6)") (class "Default")
      (node (ref "U1") (pin "6") (pinfunction "GPIO_04_6") (pintype "unspecified+no_connect"))
    )
    (net (code "64") (name "unconnected-(U1-GPIO_05-Pad7)") (class "Default")
      (node (ref "U1") (pin "7") (pinfunction "GPIO_05_7") (pintype "unspecified+no_connect"))
    )
    (net (code "65") (name "unconnected-(U1-GPIO_06-Pad8)") (class "Default")
      (node (ref "U1") (pin "8") (pinfunction "GPIO_06_8") (pintype "unspecified+no_connect"))
    )
    (net (code "66") (name "unconnected-(U1-GPIO_22-Pad27)") (class "Default")
      (node (ref "U1") (pin "27") (pinfunction "GPIO_22_27") (pintype "unspecified+no_connect"))
    )
    (net (code "67") (name "unconnected-(U1-GPIO_25-Pad37)") (class "Default")
      (node (ref "U1") (pin "37") (pinfunction "GPIO_25_37") (pintype "unspecified+no_connect"))
    )
    (net (code "68") (name "unconnected-(U1-GPIO_26-Pad38)") (class "Default")
      (node (ref "U1") (pin "38") (pinfunction "GPIO_26_38") (pintype "unspecified+no_connect"))
    )
    (net (code "69") (name "unconnected-(U1-GPIO_27-Pad39)") (class "Default")
      (node (ref "U1") (pin "39") (pinfunction "GPIO_27_39") (pintype "unspecified+no_connect"))
    )
    (net (code "70") (name "unconnected-(U1-GPIO_28-Pad40)") (class "Default")
      (node (ref "U1") (pin "40") (pinfunction "GPIO_28_40") (pintype "unspecified+no_connect"))
    )
    (net (code "71") (name "unconnected-(U1-GPIO_29-Pad41)") (class "Default")
      (node (ref "U1") (pin "41") (pinfunction "GPIO_29_41") (pintype "unspecified+no_connect"))
    )
    (net (code "72") (name "unconnected-(U1-GPIO_30-Pad42)") (class "Default")
      (node (ref "U1") (pin "42") (pinfunction "GPIO_30_42") (pintype "unspecified+no_connect"))
    )
    (net (code "73") (name "unconnected-(U1-GPIO_31-Pad43)") (class "Default")
      (node (ref "U1") (pin "43") (pinfunction "GPIO_31_43") (pintype "unspecified+no_connect"))
    )
    (net (code "74") (name "unconnected-(U4-NC-Pad1)") (class "Default")
      (node (ref "U4") (pin "1") (pinfunction "NC_1") (pintype "input+no_connect"))
    )
    (net (code "75") (name "unconnected-(U4-NC-Pad2)") (class "Default")
      (node (ref "U4") (pin "2") (pinfunction "NC_2") (pintype "input+no_connect"))
    )
    (net (code "76") (name "unconnected-(U4-NC-Pad6)") (class "Default")
      (node (ref "U4") (pin "6") (pinfunction "NC_6") (pintype "input+no_connect"))
    )
    (net (code "77") (name "unconnected-(U4-NC-Pad16)") (class "Default")
      (node (ref "U4") (pin "16") (pinfunction "NC_16") (pintype "input+no_connect"))
    )
    (net (code "78") (name "unconnected-(USB2-SBU1-PadA8)") (class "Default")
      (node (ref "USB2") (pin "A8") (pinfunction "SBU1_A8") (pintype "unspecified+no_connect"))
    )
    (net (code "79") (name "unconnected-(USB2-SBU2-PadB8)") (class "Default")
      (node (ref "USB2") (pin "B8") (pinfunction "SBU2_B8") (pintype "unspecified+no_connect"))
    )
  )
)
